# 1541-3.net
KiCad netlist of a schematic drawn in EAGLE
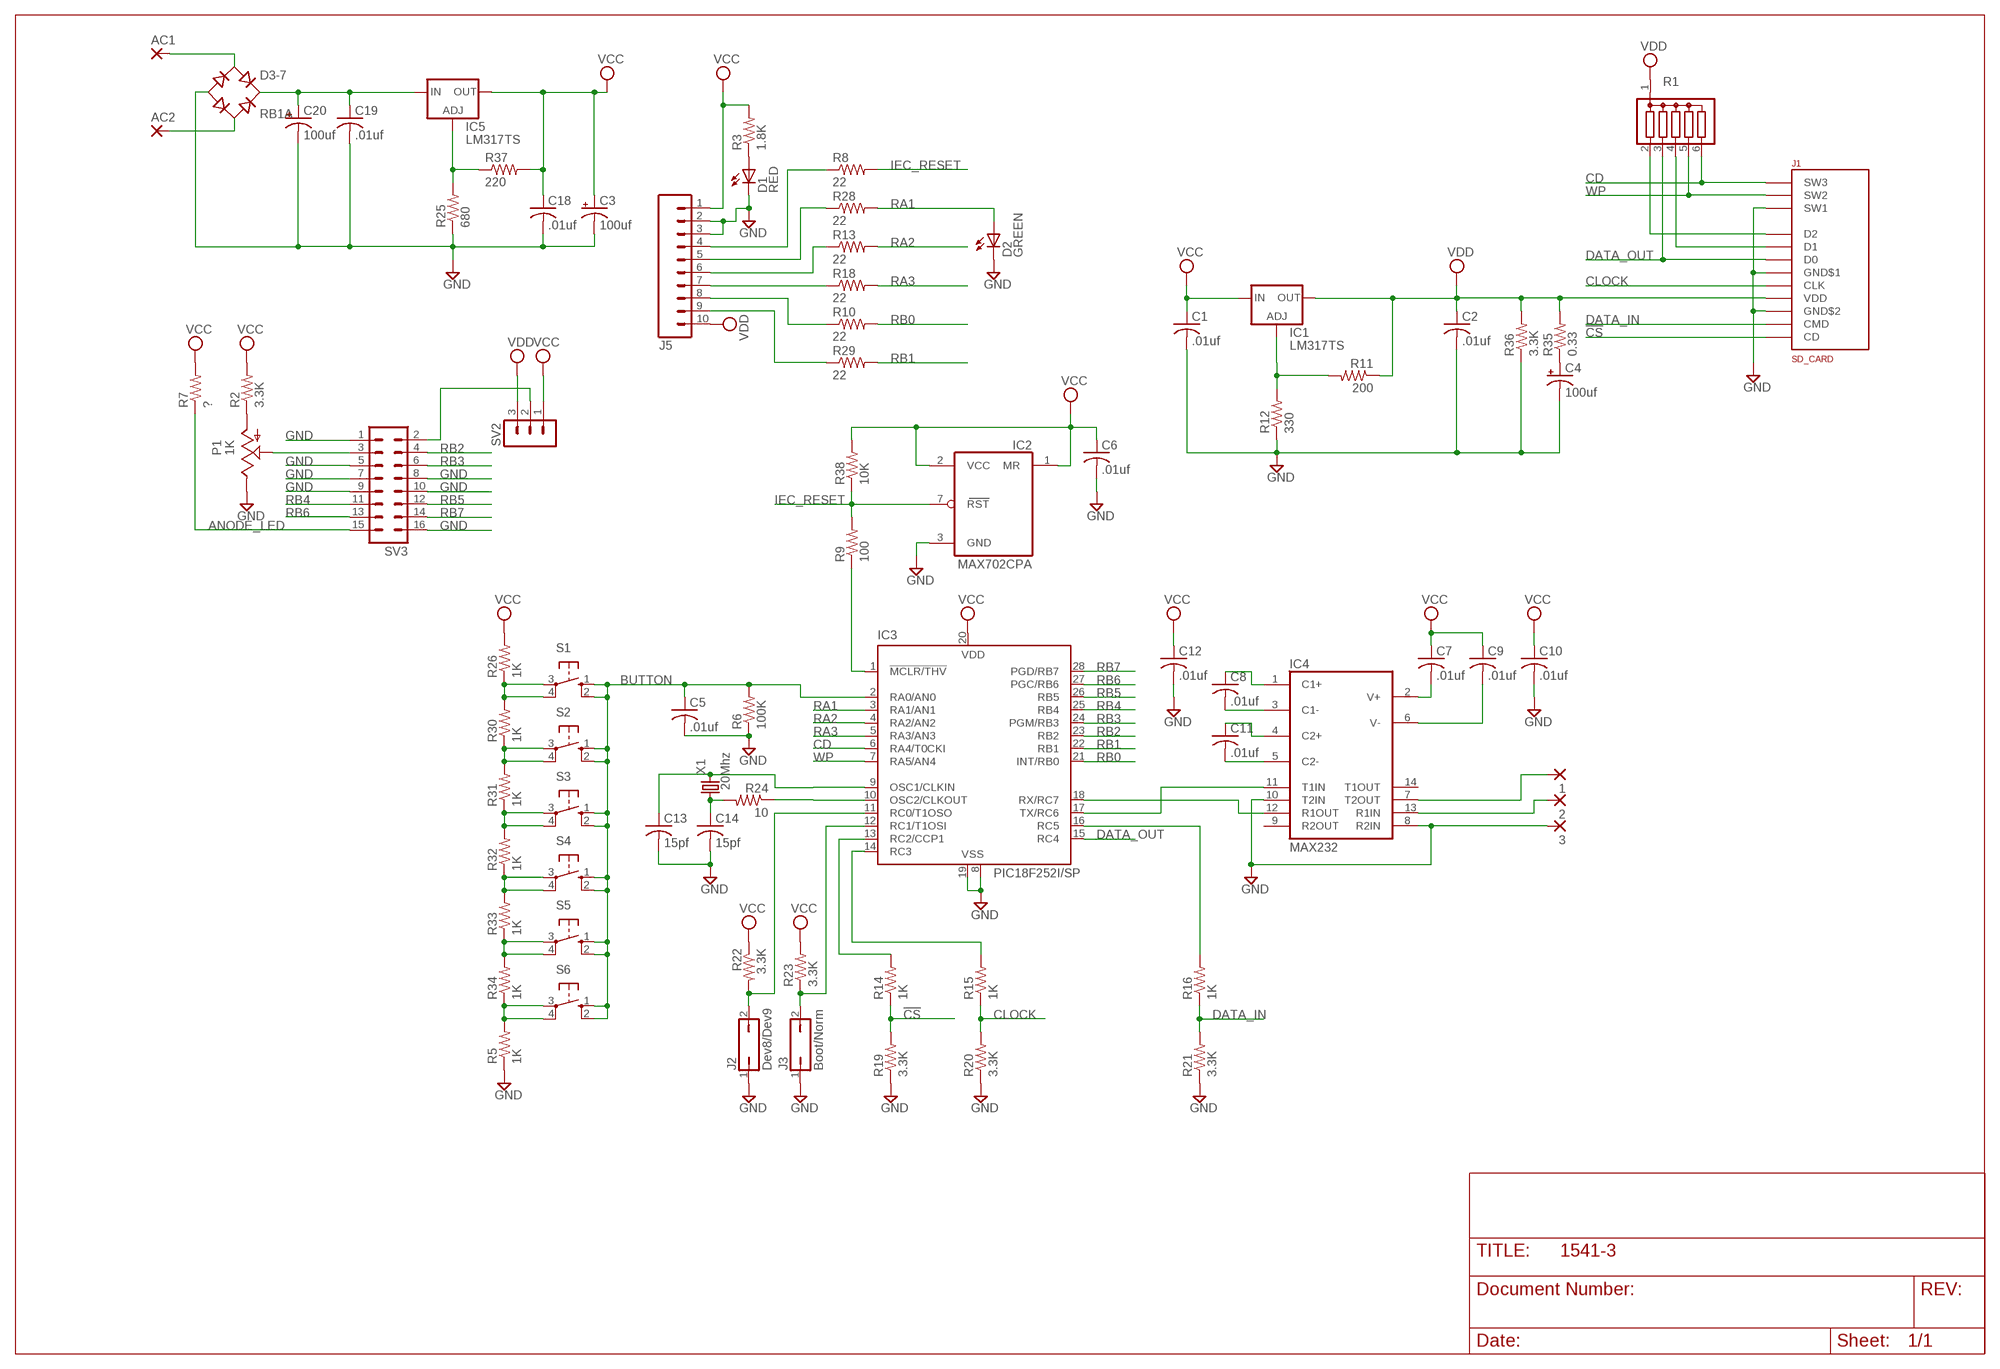
[diagram p0: schematic, sheet 1]

(export (version "E")
  (design (tool "Eeschema 10.0.6"))
  (components
    (comp (ref "1")
      (value "2,15/1,0")
      (footprint "eagle-import:2,15_1,0")
      (libsource (lib "eagle-import") (part "2,15/1,0"))
    )
    (comp (ref "2")
      (value "2,15/1,0")
      (footprint "eagle-import:2,15_1,0")
      (libsource (lib "eagle-import") (part "2,15/1,0"))
    )
    (comp (ref "3")
      (value "2,15/1,0")
      (footprint "eagle-import:2,15_1,0")
      (libsource (lib "eagle-import") (part "2,15/1,0"))
    )
    (comp (ref "AC1")
      (value "2,15/1,0")
      (footprint "eagle-import:2,15_1,0")
      (libsource (lib "eagle-import") (part "2,15/1,0"))
    )
    (comp (ref "AC2")
      (value "2,15/1,0")
      (footprint "eagle-import:2,15_1,0")
      (libsource (lib "eagle-import") (part "2,15/1,0"))
    )
    (comp (ref "C1")
      (value ".01uf")
      (footprint "eagle-import:C025-024X044")
      (libsource (lib "eagle-import") (part "C-US025-024X044"))
    )
    (comp (ref "C2")
      (value ".01uf")
      (footprint "eagle-import:C025-024X044")
      (libsource (lib "eagle-import") (part "C-US025-024X044"))
    )
    (comp (ref "C3")
      (value "100uf")
      (footprint "eagle-import:E2-5")
      (libsource (lib "eagle-import") (part "CPOL-USE2-5"))
    )
    (comp (ref "C4")
      (value "100uf")
      (footprint "eagle-import:E2-5")
      (libsource (lib "eagle-import") (part "CPOL-USE2-5"))
    )
    (comp (ref "C5")
      (value ".01uf")
      (footprint "eagle-import:C025-024X044")
      (libsource (lib "eagle-import") (part "C-US025-024X044"))
    )
    (comp (ref "C6")
      (value ".01uf")
      (footprint "eagle-import:C025-024X044")
      (libsource (lib "eagle-import") (part "C-US025-024X044"))
    )
    (comp (ref "C7")
      (value ".01uf")
      (footprint "eagle-import:C025-024X044")
      (libsource (lib "eagle-import") (part "C-US025-024X044"))
    )
    (comp (ref "C8")
      (value ".01uf")
      (footprint "eagle-import:C025-024X044")
      (libsource (lib "eagle-import") (part "C-US025-024X044"))
    )
    (comp (ref "C9")
      (value ".01uf")
      (footprint "eagle-import:C025-024X044")
      (libsource (lib "eagle-import") (part "C-US025-024X044"))
    )
    (comp (ref "C10")
      (value ".01uf")
      (footprint "eagle-import:C025-024X044")
      (libsource (lib "eagle-import") (part "C-US025-024X044"))
    )
    (comp (ref "C11")
      (value ".01uf")
      (footprint "eagle-import:C025-024X044")
      (libsource (lib "eagle-import") (part "C-US025-024X044"))
    )
    (comp (ref "C12")
      (value ".01uf")
      (footprint "eagle-import:C025-024X044")
      (libsource (lib "eagle-import") (part "C-US025-024X044"))
    )
    (comp (ref "C13")
      (value "15pf")
      (footprint "eagle-import:C025-024X044")
      (libsource (lib "eagle-import") (part "C-US025-024X044"))
    )
    (comp (ref "C14")
      (value "15pf")
      (footprint "eagle-import:C025-024X044")
      (libsource (lib "eagle-import") (part "C-US025-024X044"))
    )
    (comp (ref "C18")
      (value ".01uf")
      (footprint "eagle-import:C025-024X044")
      (libsource (lib "eagle-import") (part "C-US025-024X044"))
    )
    (comp (ref "C19")
      (value ".01uf")
      (footprint "eagle-import:C025-024X044")
      (libsource (lib "eagle-import") (part "C-US025-024X044"))
    )
    (comp (ref "C20")
      (value "100uf")
      (footprint "eagle-import:E2-5")
      (libsource (lib "eagle-import") (part "CPOL-USE2-5"))
    )
    (comp (ref "D1")
      (value "RED")
      (footprint "eagle-import:LED3MM")
      (libsource (lib "eagle-import") (part "LED3MM"))
    )
    (comp (ref "D2")
      (value "GREEN")
      (footprint "eagle-import:LED3MM")
      (libsource (lib "eagle-import") (part "LED3MM"))
    )
    (comp (ref "D3-7")
      (value "RB1A")
      (footprint "eagle-import:RB1A")
      (libsource (lib "eagle-import") (part "RB1A"))
    )
    (comp (ref "IC1")
      (value "LM317TS")
      (footprint "eagle-import:317TS")
      (libsource (lib "eagle-import") (part "LM317TS"))
    )
    (comp (ref "IC2")
      (value "MAX702CPA")
      (footprint "eagle-import:DIL08")
      (fields (field (name "MF") "MAXIM") (field (name "MPN") "MAX702CPA+"))
      (libsource (lib "eagle-import") (part "MAX702CPA"))
    )
    (comp (ref "IC3")
      (value "PIC18F252I/SP")
      (footprint "eagle-import:DIL28-3")
      (fields (field (name "MF") "MICROCHIP") (field (name "MPN") "PIC16F870-I/SP"))
      (libsource (lib "eagle-import") (part "PIC16870PF"))
    )
    (comp (ref "IC4")
      (value "MAX232")
      (footprint "eagle-import:DIL16")
      (fields (field (name "MF") "MAXIM") (field (name "MPN") "MAX232ACPE+"))
      (libsource (lib "eagle-import") (part "MAX232"))
    )
    (comp (ref "IC5")
      (value "LM317TS")
      (footprint "eagle-import:317TS")
      (libsource (lib "eagle-import") (part "LM317TS"))
    )
    (comp (ref "J1")
      (value "SD_CARD")
      (footprint "eagle-import:SD_CARD")
      (libsource (lib "eagle-import") (part "SD_CARD"))
    )
    (comp (ref "J2")
      (value "Dev8/Dev9")
      (footprint "eagle-import:JP1")
      (libsource (lib "eagle-import") (part "JP1Q"))
    )
    (comp (ref "J3")
      (value "Boot/Norm")
      (footprint "eagle-import:JP1")
      (libsource (lib "eagle-import") (part "JP1Q"))
    )
    (comp (ref "J5")
      (value "M10")
      (footprint "eagle-import:10P")
      (libsource (lib "eagle-import") (part "M10"))
    )
    (comp (ref "P1")
      (value "1K")
      (footprint "eagle-import:LI10")
      (libsource (lib "eagle-import") (part "TRIM_US-LI10"))
    )
    (comp (ref "R1")
      (value "G05R")
      (footprint "eagle-import:SIL6")
      (libsource (lib "eagle-import") (part "G05R"))
    )
    (comp (ref "R2")
      (value "3.3K")
      (footprint "eagle-import:0207_2V")
      (libsource (lib "eagle-import") (part "R-US_0207/2V"))
    )
    (comp (ref "R3")
      (value "1.8K")
      (footprint "eagle-import:0207_2V")
      (libsource (lib "eagle-import") (part "R-US_0207/2V"))
    )
    (comp (ref "R5")
      (value "1K")
      (footprint "eagle-import:0207_2V")
      (libsource (lib "eagle-import") (part "R-US_0207/2V"))
    )
    (comp (ref "R6")
      (value "100K")
      (footprint "eagle-import:0207_2V")
      (libsource (lib "eagle-import") (part "R-US_0207/2V"))
    )
    (comp (ref "R7")
      (value "?")
      (footprint "eagle-import:0207_2V")
      (libsource (lib "eagle-import") (part "R-US_0207/2V"))
    )
    (comp (ref "R8")
      (value "22")
      (footprint "eagle-import:0207_2V")
      (libsource (lib "eagle-import") (part "R-US_0207/2V"))
    )
    (comp (ref "R9")
      (value "100")
      (footprint "eagle-import:0207_2V")
      (libsource (lib "eagle-import") (part "R-US_0207/2V"))
    )
    (comp (ref "R10")
      (value "22")
      (footprint "eagle-import:0207_2V")
      (libsource (lib "eagle-import") (part "R-US_0207/2V"))
    )
    (comp (ref "R11")
      (value "200")
      (footprint "eagle-import:0207_2V")
      (libsource (lib "eagle-import") (part "R-US_0207/2V"))
    )
    (comp (ref "R12")
      (value "330")
      (footprint "eagle-import:0207_2V")
      (libsource (lib "eagle-import") (part "R-US_0207/2V"))
    )
    (comp (ref "R13")
      (value "22")
      (footprint "eagle-import:0207_2V")
      (libsource (lib "eagle-import") (part "R-US_0207/2V"))
    )
    (comp (ref "R14")
      (value "1K")
      (footprint "eagle-import:0207_2V")
      (libsource (lib "eagle-import") (part "R-US_0207/2V"))
    )
    (comp (ref "R15")
      (value "1K")
      (footprint "eagle-import:0207_2V")
      (libsource (lib "eagle-import") (part "R-US_0207/2V"))
    )
    (comp (ref "R16")
      (value "1K")
      (footprint "eagle-import:0207_2V")
      (libsource (lib "eagle-import") (part "R-US_0207/2V"))
    )
    (comp (ref "R18")
      (value "22")
      (footprint "eagle-import:0207_2V")
      (libsource (lib "eagle-import") (part "R-US_0207/2V"))
    )
    (comp (ref "R19")
      (value "3.3K")
      (footprint "eagle-import:0207_2V")
      (libsource (lib "eagle-import") (part "R-US_0207/2V"))
    )
    (comp (ref "R20")
      (value "3.3K")
      (footprint "eagle-import:0207_2V")
      (libsource (lib "eagle-import") (part "R-US_0207/2V"))
    )
    (comp (ref "R21")
      (value "3.3K")
      (footprint "eagle-import:0207_2V")
      (libsource (lib "eagle-import") (part "R-US_0207/2V"))
    )
    (comp (ref "R22")
      (value "3.3K")
      (footprint "eagle-import:0207_2V")
      (libsource (lib "eagle-import") (part "R-US_0207/2V"))
    )
    (comp (ref "R23")
      (value "3.3K")
      (footprint "eagle-import:0207_2V")
      (libsource (lib "eagle-import") (part "R-US_0207/2V"))
    )
    (comp (ref "R24")
      (value "10")
      (footprint "eagle-import:0207_2V")
      (libsource (lib "eagle-import") (part "R-US_0207/2V"))
    )
    (comp (ref "R25")
      (value "680")
      (footprint "eagle-import:0207_2V")
      (libsource (lib "eagle-import") (part "R-US_0207/2V"))
    )
    (comp (ref "R26")
      (value "1K")
      (footprint "eagle-import:0207_2V")
      (libsource (lib "eagle-import") (part "R-US_0207/2V"))
    )
    (comp (ref "R28")
      (value "22")
      (footprint "eagle-import:0207_2V")
      (libsource (lib "eagle-import") (part "R-US_0207/2V"))
    )
    (comp (ref "R29")
      (value "22")
      (footprint "eagle-import:0207_2V")
      (libsource (lib "eagle-import") (part "R-US_0207/2V"))
    )
    (comp (ref "R30")
      (value "1K")
      (footprint "eagle-import:0207_2V")
      (libsource (lib "eagle-import") (part "R-US_0207/2V"))
    )
    (comp (ref "R31")
      (value "1K")
      (footprint "eagle-import:0207_2V")
      (libsource (lib "eagle-import") (part "R-US_0207/2V"))
    )
    (comp (ref "R32")
      (value "1K")
      (footprint "eagle-import:0207_2V")
      (libsource (lib "eagle-import") (part "R-US_0207/2V"))
    )
    (comp (ref "R33")
      (value "1K")
      (footprint "eagle-import:0207_2V")
      (libsource (lib "eagle-import") (part "R-US_0207/2V"))
    )
    (comp (ref "R34")
      (value "1K")
      (footprint "eagle-import:0207_2V")
      (libsource (lib "eagle-import") (part "R-US_0207/2V"))
    )
    (comp (ref "R35")
      (value "0.33")
      (footprint "eagle-import:0207_2V")
      (libsource (lib "eagle-import") (part "R-US_0207/2V"))
    )
    (comp (ref "R36")
      (value "3.3K")
      (footprint "eagle-import:0207_2V")
      (libsource (lib "eagle-import") (part "R-US_0207/2V"))
    )
    (comp (ref "R37")
      (value "220")
      (footprint "eagle-import:0207_2V")
      (libsource (lib "eagle-import") (part "R-US_0207/2V"))
    )
    (comp (ref "R38")
      (value "10K")
      (footprint "eagle-import:0207_2V")
      (libsource (lib "eagle-import") (part "R-US_0207/2V"))
    )
    (comp (ref "S1")
      (value "10-XX")
      (footprint "eagle-import:B3F-10XX")
      (fields (field (name "MPN") "B3F-1000"))
      (libsource (lib "eagle-import") (part "10-XX"))
    )
    (comp (ref "S2")
      (value "10-XX")
      (footprint "eagle-import:B3F-10XX")
      (fields (field (name "MPN") "B3F-1000"))
      (libsource (lib "eagle-import") (part "10-XX"))
    )
    (comp (ref "S3")
      (value "10-XX")
      (footprint "eagle-import:B3F-10XX")
      (fields (field (name "MPN") "B3F-1000"))
      (libsource (lib "eagle-import") (part "10-XX"))
    )
    (comp (ref "S4")
      (value "10-XX")
      (footprint "eagle-import:B3F-10XX")
      (fields (field (name "MPN") "B3F-1000"))
      (libsource (lib "eagle-import") (part "10-XX"))
    )
    (comp (ref "S5")
      (value "10-XX")
      (footprint "eagle-import:B3F-10XX")
      (fields (field (name "MPN") "B3F-1000"))
      (libsource (lib "eagle-import") (part "10-XX"))
    )
    (comp (ref "S6")
      (value "10-XX")
      (footprint "eagle-import:B3F-10XX")
      (fields (field (name "MPN") "B3F-1000"))
      (libsource (lib "eagle-import") (part "10-XX"))
    )
    (comp (ref "SV2")
      (value "MA03-1")
      (footprint "eagle-import:MA03-1")
      (libsource (lib "eagle-import") (part "MA03-1"))
    )
    (comp (ref "SV3")
      (value "ML16")
      (footprint "eagle-import:ML16")
      (libsource (lib "eagle-import") (part "ML16"))
    )
    (comp (ref "X1")
      (value "20Mhz")
      (footprint "eagle-import:HC49U70")
      (libsource (lib "eagle-import") (part "CRYSTALHC49U70"))
    )
  )
  (nets
    (net (code "1") (name "/ANODE_LED") (class "Default")
      (node (ref "R7") (pin "1") (pinfunction "1_1") (pintype "passive"))
      (node (ref "SV3") (pin "15") (pinfunction "15_15") (pintype "passive"))
    )
    (net (code "2") (name "/BUTTON") (class "Default")
      (node (ref "C5") (pin "1") (pinfunction "1_1") (pintype "passive"))
      (node (ref "IC3") (pin "2") (pinfunction "RA0/AN0_2") (pintype "bidirectional"))
      (node (ref "R6") (pin "2") (pinfunction "2_2") (pintype "passive"))
      (node (ref "S1") (pin "1") (pinfunction "S_1") (pintype "passive"))
      (node (ref "S1") (pin "2") (pinfunction "S1_2") (pintype "passive"))
      (node (ref "S2") (pin "1") (pinfunction "S_1") (pintype "passive"))
      (node (ref "S2") (pin "2") (pinfunction "S1_2") (pintype "passive"))
      (node (ref "S3") (pin "1") (pinfunction "S_1") (pintype "passive"))
      (node (ref "S3") (pin "2") (pinfunction "S1_2") (pintype "passive"))
      (node (ref "S4") (pin "1") (pinfunction "S_1") (pintype "passive"))
      (node (ref "S4") (pin "2") (pinfunction "S1_2") (pintype "passive"))
      (node (ref "S5") (pin "1") (pinfunction "S_1") (pintype "passive"))
      (node (ref "S5") (pin "2") (pinfunction "S1_2") (pintype "passive"))
      (node (ref "S6") (pin "1") (pinfunction "S_1") (pintype "passive"))
      (node (ref "S6") (pin "2") (pinfunction "S1_2") (pintype "passive"))
    )
    (net (code "3") (name "/CD") (class "Default")
      (node (ref "IC3") (pin "6") (pinfunction "RA4/T0CKI_6") (pintype "bidirectional"))
      (node (ref "J1") (pin "SW3") (pinfunction "SW3_SW3") (pintype "output"))
      (node (ref "R1") (pin "6") (pinfunction "6_6") (pintype "passive"))
    )
    (net (code "4") (name "/CLOCK") (class "Default")
      (node (ref "J1") (pin "CLK") (pinfunction "CLK_CLK") (pintype "input"))
      (node (ref "R15") (pin "1") (pinfunction "1_1") (pintype "passive"))
      (node (ref "R20") (pin "2") (pinfunction "2_2") (pintype "passive"))
    )
    (net (code "5") (name "/DATA_IN") (class "Default")
      (node (ref "J1") (pin "CMD") (pinfunction "CMD_CMD") (pintype "input"))
      (node (ref "R16") (pin "1") (pinfunction "1_1") (pintype "passive"))
      (node (ref "R21") (pin "2") (pinfunction "2_2") (pintype "passive"))
    )
    (net (code "6") (name "/DATA_OUT") (class "Default")
      (node (ref "IC3") (pin "15") (pinfunction "RC4_15") (pintype "bidirectional"))
      (node (ref "J1") (pin "DAT0") (pinfunction "D0_DAT0") (pintype "output"))
      (node (ref "R1") (pin "3") (pinfunction "3_3") (pintype "passive"))
    )
    (net (code "7") (name "/IEC_RESET") (class "Default")
      (node (ref "IC2") (pin "7") (pinfunction "RST_7") (pintype "output"))
      (node (ref "R38") (pin "1") (pinfunction "1_1") (pintype "passive"))
      (node (ref "R8") (pin "2") (pinfunction "2_2") (pintype "passive"))
      (node (ref "R9") (pin "2") (pinfunction "2_2") (pintype "passive"))
    )
    (net (code "8") (name "/RA1") (class "Default")
      (node (ref "D2") (pin "A") (pinfunction "A_A") (pintype "passive"))
      (node (ref "IC3") (pin "3") (pinfunction "RA1/AN1_3") (pintype "bidirectional"))
      (node (ref "R28") (pin "2") (pinfunction "2_2") (pintype "passive"))
    )
    (net (code "9") (name "/RA2") (class "Default")
      (node (ref "IC3") (pin "4") (pinfunction "RA2/AN2_4") (pintype "bidirectional"))
      (node (ref "R13") (pin "2") (pinfunction "2_2") (pintype "passive"))
    )
    (net (code "10") (name "/RA3") (class "Default")
      (node (ref "IC3") (pin "5") (pinfunction "RA3/AN3_5") (pintype "bidirectional"))
      (node (ref "R18") (pin "2") (pinfunction "2_2") (pintype "passive"))
    )
    (net (code "11") (name "/RB0") (class "Default")
      (node (ref "IC3") (pin "21") (pinfunction "INT/RB0_21") (pintype "bidirectional"))
      (node (ref "R10") (pin "2") (pinfunction "2_2") (pintype "passive"))
    )
    (net (code "12") (name "/RB1") (class "Default")
      (node (ref "IC3") (pin "22") (pinfunction "RB1_22") (pintype "bidirectional"))
      (node (ref "R29") (pin "2") (pinfunction "2_2") (pintype "passive"))
    )
    (net (code "13") (name "/RB2") (class "Default")
      (node (ref "IC3") (pin "23") (pinfunction "RB2_23") (pintype "bidirectional"))
      (node (ref "SV3") (pin "4") (pinfunction "4_4") (pintype "passive"))
    )
    (net (code "14") (name "/RB3") (class "Default")
      (node (ref "IC3") (pin "24") (pinfunction "PGM/RB3_24") (pintype "bidirectional"))
      (node (ref "SV3") (pin "6") (pinfunction "6_6") (pintype "passive"))
    )
    (net (code "15") (name "/RB4") (class "Default")
      (node (ref "IC3") (pin "25") (pinfunction "RB4_25") (pintype "bidirectional"))
      (node (ref "SV3") (pin "11") (pinfunction "11_11") (pintype "passive"))
    )
    (net (code "16") (name "/RB5") (class "Default")
      (node (ref "IC3") (pin "26") (pinfunction "RB5_26") (pintype "bidirectional"))
      (node (ref "SV3") (pin "12") (pinfunction "12_12") (pintype "passive"))
    )
    (net (code "17") (name "/RB6") (class "Default")
      (node (ref "IC3") (pin "27") (pinfunction "PGC/RB6_27") (pintype "bidirectional"))
      (node (ref "SV3") (pin "13") (pinfunction "13_13") (pintype "passive"))
    )
    (net (code "18") (name "/RB7") (class "Default")
      (node (ref "IC3") (pin "28") (pinfunction "PGD/RB7_28") (pintype "bidirectional"))
      (node (ref "SV3") (pin "14") (pinfunction "14_14") (pintype "passive"))
    )
    (net (code "19") (name "/WP") (class "Default")
      (node (ref "IC3") (pin "7") (pinfunction "RA5/AN4_7") (pintype "bidirectional"))
      (node (ref "J1") (pin "SW2") (pinfunction "SW2_SW2") (pintype "output"))
      (node (ref "R1") (pin "5") (pinfunction "5_5") (pintype "passive"))
    )
    (net (code "20") (name "/~{CS}") (class "Default")
      (node (ref "J1") (pin "DAT3") (pinfunction "CD_DAT3") (pintype "input"))
      (node (ref "R14") (pin "1") (pinfunction "1_1") (pintype "passive"))
      (node (ref "R19") (pin "2") (pinfunction "2_2") (pintype "passive"))
    )
    (net (code "21") (name "GND") (class "Default")
      (node (ref "3") (pin "1") (pinfunction "P_1") (pintype "passive"))
      (node (ref "C1") (pin "2") (pinfunction "2_2") (pintype "passive"))
      (node (ref "C10") (pin "2") (pinfunction "2_2") (pintype "passive"))
      (node (ref "C12") (pin "2") (pinfunction "2_2") (pintype "passive"))
      (node (ref "C13") (pin "2") (pinfunction "2_2") (pintype "passive"))
      (node (ref "C14") (pin "2") (pinfunction "2_2") (pintype "passive"))
      (node (ref "C18") (pin "2") (pinfunction "2_2") (pintype "passive"))
      (node (ref "C19") (pin "2") (pinfunction "2_2") (pintype "passive"))
      (node (ref "C2") (pin "2") (pinfunction "2_2") (pintype "passive"))
      (node (ref "C20") (pin "-") (pinfunction "-_-") (pintype "passive"))
      (node (ref "C3") (pin "-") (pinfunction "-_-") (pintype "passive"))
      (node (ref "C4") (pin "-") (pinfunction "-_-") (pintype "passive"))
      (node (ref "C5") (pin "2") (pinfunction "2_2") (pintype "passive"))
      (node (ref "C6") (pin "2") (pinfunction "2_2") (pintype "passive"))
      (node (ref "D1") (pin "K") (pinfunction "C_K") (pintype "passive"))
      (node (ref "D2") (pin "K") (pinfunction "C_K") (pintype "passive"))
      (node (ref "D3-7") (pin "-") (pinfunction "-_-") (pintype "passive"))
      (node (ref "IC2") (pin "3") (pinfunction "GND_3") (pintype "power_in"))
      (node (ref "IC3") (pin "19") (pinfunction "VSS_19") (pintype "power_in"))
      (node (ref "IC3") (pin "8") (pinfunction "VSS_8") (pintype "power_in"))
      (node (ref "IC4") (pin "10") (pinfunction "T2IN_10") (pintype "input"))
      (node (ref "IC4") (pin "8") (pinfunction "R2IN_8") (pintype "input"))
      (node (ref "J1") (pin "SW1") (pinfunction "SW1_SW1") (pintype "input"))
      (node (ref "J1") (pin "VSS$1") (pinfunction "GND$1_VSS$1") (pintype "power_in"))
      (node (ref "J1") (pin "VSS$2") (pinfunction "GND$2_VSS$2") (pintype "power_in"))
      (node (ref "J2") (pin "1") (pinfunction "1_1") (pintype "passive"))
      (node (ref "J3") (pin "1") (pinfunction "1_1") (pintype "passive"))
      (node (ref "J5") (pin "2") (pinfunction "2_2") (pintype "passive"))
      (node (ref "J5") (pin "3") (pinfunction "3_3") (pintype "passive"))
      (node (ref "P1") (pin "E") (pinfunction "E_E") (pintype "passive"))
      (node (ref "R12") (pin "1") (pinfunction "1_1") (pintype "passive"))
      (node (ref "R19") (pin "1") (pinfunction "1_1") (pintype "passive"))
      (node (ref "R20") (pin "1") (pinfunction "1_1") (pintype "passive"))
      (node (ref "R21") (pin "1") (pinfunction "1_1") (pintype "passive"))
      (node (ref "R25") (pin "1") (pinfunction "1_1") (pintype "passive"))
      (node (ref "R36") (pin "1") (pinfunction "1_1") (pintype "passive"))
      (node (ref "R5") (pin "1") (pinfunction "1_1") (pintype "passive"))
      (node (ref "R6") (pin "1") (pinfunction "1_1") (pintype "passive"))
      (node (ref "SV3") (pin "1") (pinfunction "1_1") (pintype "passive"))
      (node (ref "SV3") (pin "10") (pinfunction "10_10") (pintype "passive"))
      (node (ref "SV3") (pin "16") (pinfunction "16_16") (pintype "passive"))
      (node (ref "SV3") (pin "5") (pinfunction "5_5") (pintype "passive"))
      (node (ref "SV3") (pin "7") (pinfunction "7_7") (pintype "passive"))
      (node (ref "SV3") (pin "8") (pinfunction "8_8") (pintype "passive"))
      (node (ref "SV3") (pin "9") (pinfunction "9_9") (pintype "passive"))
    )
    (net (code "22") (name "Net-(1-P)") (class "Default")
      (node (ref "1") (pin "1") (pinfunction "P_1") (pintype "passive"))
      (node (ref "IC4") (pin "7") (pinfunction "T2OUT_7") (pintype "output"))
    )
    (net (code "23") (name "Net-(2-P)") (class "Default")
      (node (ref "2") (pin "1") (pinfunction "P_1") (pintype "passive"))
      (node (ref "IC4") (pin "13") (pinfunction "R1IN_13") (pintype "input"))
    )
    (net (code "24") (name "Net-(AC1-P)") (class "Default")
      (node (ref "AC1") (pin "1") (pinfunction "P_1") (pintype "passive"))
      (node (ref "D3-7") (pin "AC1") (pinfunction "AC1_AC1") (pintype "passive"))
    )
    (net (code "25") (name "Net-(AC2-P)") (class "Default")
      (node (ref "AC2") (pin "1") (pinfunction "P_1") (pintype "passive"))
      (node (ref "D3-7") (pin "AC2") (pinfunction "AC2_AC2") (pintype "passive"))
    )
    (net (code "26") (name "Net-(C4-Pad+)") (class "Default")
      (node (ref "C4") (pin "+") (pinfunction "+_+") (pintype "passive"))
      (node (ref "R35") (pin "1") (pinfunction "1_1") (pintype "passive"))
    )
    (net (code "27") (name "Net-(C14-Pad1)") (class "Default")
      (node (ref "C14") (pin "1") (pinfunction "1_1") (pintype "passive"))
      (node (ref "R24") (pin "2") (pinfunction "2_2") (pintype "passive"))
      (node (ref "X1") (pin "1") (pinfunction "1_1") (pintype "passive"))
    )
    (net (code "28") (name "Net-(D1-PadA)") (class "Default")
      (node (ref "D1") (pin "A") (pinfunction "A_A") (pintype "passive"))
      (node (ref "R3") (pin "1") (pinfunction "1_1") (pintype "passive"))
    )
    (net (code "29") (name "Net-(IC1-ADJ)") (class "Default")
      (node (ref "IC1") (pin "1") (pinfunction "ADJ_1") (pintype "input"))
      (node (ref "R11") (pin "2") (pinfunction "2_2") (pintype "passive"))
      (node (ref "R12") (pin "2") (pinfunction "2_2") (pintype "passive"))
    )
    (net (code "30") (name "Net-(IC3-OSC1{slash}CLKIN)") (class "Default")
      (node (ref "C13") (pin "1") (pinfunction "1_1") (pintype "passive"))
      (node (ref "IC3") (pin "9") (pinfunction "OSC1/CLKIN_9") (pintype "input"))
      (node (ref "X1") (pin "2") (pinfunction "2_2") (pintype "passive"))
    )
    (net (code "31") (name "Net-(IC3-OSC2{slash}CLKOUT)") (class "Default")
      (node (ref "IC3") (pin "10") (pinfunction "OSC2/CLKOUT_10") (pintype "output"))
      (node (ref "R24") (pin "1") (pinfunction "1_1") (pintype "passive"))
    )
    (net (code "32") (name "Net-(IC3-RC0{slash}T1OSO)") (class "Default")
      (node (ref "IC3") (pin "11") (pinfunction "RC0/T1OSO_11") (pintype "bidirectional"))
      (node (ref "J2") (pin "2") (pinfunction "2_2") (pintype "passive"))
      (node (ref "R22") (pin "2") (pinfunction "2_2") (pintype "passive"))
    )
    (net (code "33") (name "Net-(IC3-RC1{slash}T1OSI)") (class "Default")
      (node (ref "IC3") (pin "12") (pinfunction "RC1/T1OSI_12") (pintype "bidirectional"))
      (node (ref "J3") (pin "2") (pinfunction "2_2") (pintype "passive"))
      (node (ref "R23") (pin "1") (pinfunction "1_1") (pintype "passive"))
    )
    (net (code "34") (name "Net-(IC3-RC2{slash}CCP1)") (class "Default")
      (node (ref "IC3") (pin "13") (pinfunction "RC2/CCP1_13") (pintype "bidirectional"))
      (node (ref "R14") (pin "2") (pinfunction "2_2") (pintype "passive"))
    )
    (net (code "35") (name "Net-(IC3-RC3)") (class "Default")
      (node (ref "IC3") (pin "14") (pinfunction "RC3_14") (pintype "bidirectional"))
      (node (ref "R15") (pin "2") (pinfunction "2_2") (pintype "passive"))
    )
    (net (code "36") (name "Net-(IC3-RC5)") (class "Default")
      (node (ref "IC3") (pin "16") (pinfunction "RC5_16") (pintype "bidirectional"))
      (node (ref "R16") (pin "2") (pinfunction "2_2") (pintype "passive"))
    )
    (net (code "37") (name "Net-(IC3-RX{slash}RC7)") (class "Default")
      (node (ref "IC3") (pin "18") (pinfunction "RX/RC7_18") (pintype "bidirectional"))
      (node (ref "IC4") (pin "12") (pinfunction "R1OUT_12") (pintype "output"))
    )
    (net (code "38") (name "Net-(IC3-TX{slash}RC6)") (class "Default")
      (node (ref "IC3") (pin "17") (pinfunction "TX/RC6_17") (pintype "bidirectional"))
      (node (ref "IC4") (pin "11") (pinfunction "T1IN_11") (pintype "input"))
    )
    (net (code "39") (name "Net-(IC3-~{MCLR{slash}THV})") (class "Default")
      (node (ref "IC3") (pin "1") (pinfunction "~{MCLR/THV}_1") (pintype "input"))
      (node (ref "R9") (pin "1") (pinfunction "1_1") (pintype "passive"))
    )
    (net (code "40") (name "Net-(IC4A-C1+)") (class "Default")
      (node (ref "C8") (pin "1") (pinfunction "1_1") (pintype "passive"))
      (node (ref "IC4") (pin "1") (pinfunction "C1+_1") (pintype "bidirectional"))
    )
    (net (code "41") (name "Net-(IC4A-C1-)") (class "Default")
      (node (ref "C8") (pin "2") (pinfunction "2_2") (pintype "passive"))
      (node (ref "IC4") (pin "3") (pinfunction "C1-_3") (pintype "bidirectional"))
    )
    (net (code "42") (name "Net-(IC4A-C2+)") (class "Default")
      (node (ref "C11") (pin "1") (pinfunction "1_1") (pintype "passive"))
      (node (ref "IC4") (pin "4") (pinfunction "C2+_4") (pintype "bidirectional"))
    )
    (net (code "43") (name "Net-(IC4A-C2-)") (class "Default")
      (node (ref "C11") (pin "2") (pinfunction "2_2") (pintype "passive"))
      (node (ref "IC4") (pin "5") (pinfunction "C2-_5") (pintype "bidirectional"))
    )
    (net (code "44") (name "Net-(IC4A-V+)") (class "Default")
      (node (ref "C7") (pin "2") (pinfunction "2_2") (pintype "passive"))
      (node (ref "IC4") (pin "2") (pinfunction "V+_2") (pintype "bidirectional"))
    )
    (net (code "45") (name "Net-(IC4A-V-)") (class "Default")
      (node (ref "C9") (pin "2") (pinfunction "2_2") (pintype "passive"))
      (node (ref "IC4") (pin "6") (pinfunction "V-_6") (pintype "bidirectional"))
    )
    (net (code "46") (name "Net-(IC5-ADJ)") (class "Default")
      (node (ref "IC5") (pin "1") (pinfunction "ADJ_1") (pintype "input"))
      (node (ref "R25") (pin "2") (pinfunction "2_2") (pintype "passive"))
      (node (ref "R37") (pin "1") (pinfunction "1_1") (pintype "passive"))
    )
    (net (code "47") (name "Net-(IC5-IN)") (class "Default")
      (node (ref "C19") (pin "1") (pinfunction "1_1") (pintype "passive"))
      (node (ref "C20") (pin "+") (pinfunction "+_+") (pintype "passive"))
      (node (ref "D3-7") (pin "+") (pinfunction "+_+") (pintype "passive"))
      (node (ref "IC5") (pin "3") (pinfunction "IN_3") (pintype "input"))
    )
    (net (code "48") (name "Net-(J1-D1)") (class "Default")
      (node (ref "J1") (pin "DAT1") (pinfunction "D1_DAT1") (pintype "output"))
      (node (ref "R1") (pin "4") (pinfunction "4_4") (pintype "passive"))
    )
    (net (code "49") (name "Net-(J1-D2)") (class "Default")
      (node (ref "J1") (pin "DAT2") (pinfunction "D2_DAT2") (pintype "output"))
      (node (ref "R1") (pin "2") (pinfunction "2_2") (pintype "passive"))
    )
    (net (code "50") (name "Net-(J5-Pad4)") (class "Default")
      (node (ref "J5") (pin "4") (pinfunction "4_4") (pintype "passive"))
      (node (ref "R8") (pin "1") (pinfunction "1_1") (pintype "passive"))
    )
    (net (code "51") (name "Net-(J5-Pad5)") (class "Default")
      (node (ref "J5") (pin "5") (pinfunction "5_5") (pintype "passive"))
      (node (ref "R28") (pin "1") (pinfunction "1_1") (pintype "passive"))
    )
    (net (code "52") (name "Net-(J5-Pad6)") (class "Default")
      (node (ref "J5") (pin "6") (pinfunction "6_6") (pintype "passive"))
      (node (ref "R13") (pin "1") (pinfunction "1_1") (pintype "passive"))
    )
    (net (code "53") (name "Net-(J5-Pad7)") (class "Default")
      (node (ref "J5") (pin "7") (pinfunction "7_7") (pintype "passive"))
      (node (ref "R18") (pin "1") (pinfunction "1_1") (pintype "passive"))
    )
    (net (code "54") (name "Net-(J5-Pad8)") (class "Default")
      (node (ref "J5") (pin "8") (pinfunction "8_8") (pintype "passive"))
      (node (ref "R10") (pin "1") (pinfunction "1_1") (pintype "passive"))
    )
    (net (code "55") (name "Net-(J5-Pad9)") (class "Default")
      (node (ref "J5") (pin "9") (pinfunction "9_9") (pintype "passive"))
      (node (ref "R29") (pin "1") (pinfunction "1_1") (pintype "passive"))
    )
    (net (code "56") (name "Net-(P1-PadA)") (class "Default")
      (node (ref "P1") (pin "A") (pinfunction "A_A") (pintype "passive"))
      (node (ref "R2") (pin "1") (pinfunction "1_1") (pintype "passive"))
    )
    (net (code "57") (name "Net-(P1-PadS)") (class "Default")
      (node (ref "P1") (pin "S") (pinfunction "S_S") (pintype "passive"))
      (node (ref "SV3") (pin "3") (pinfunction "3_3") (pintype "passive"))
    )
    (net (code "58") (name "Net-(S1-P)") (class "Default")
      (node (ref "R26") (pin "1") (pinfunction "1_1") (pintype "passive"))
      (node (ref "R30") (pin "2") (pinfunction "2_2") (pintype "passive"))
      (node (ref "S1") (pin "3") (pinfunction "P_3") (pintype "passive"))
      (node (ref "S1") (pin "4") (pinfunction "P1_4") (pintype "passive"))
    )
    (net (code "59") (name "Net-(S2-P)") (class "Default")
      (node (ref "R30") (pin "1") (pinfunction "1_1") (pintype "passive"))
      (node (ref "R31") (pin "2") (pinfunction "2_2") (pintype "passive"))
      (node (ref "S2") (pin "3") (pinfunction "P_3") (pintype "passive"))
      (node (ref "S2") (pin "4") (pinfunction "P1_4") (pintype "passive"))
    )
    (net (code "60") (name "Net-(S3-P)") (class "Default")
      (node (ref "R31") (pin "1") (pinfunction "1_1") (pintype "passive"))
      (node (ref "R32") (pin "2") (pinfunction "2_2") (pintype "passive"))
      (node (ref "S3") (pin "3") (pinfunction "P_3") (pintype "passive"))
      (node (ref "S3") (pin "4") (pinfunction "P1_4") (pintype "passive"))
    )
    (net (code "61") (name "Net-(S4-P)") (class "Default")
      (node (ref "R32") (pin "1") (pinfunction "1_1") (pintype "passive"))
      (node (ref "R33") (pin "2") (pinfunction "2_2") (pintype "passive"))
      (node (ref "S4") (pin "3") (pinfunction "P_3") (pintype "passive"))
      (node (ref "S4") (pin "4") (pinfunction "P1_4") (pintype "passive"))
    )
    (net (code "62") (name "Net-(S5-P)") (class "Default")
      (node (ref "R33") (pin "1") (pinfunction "1_1") (pintype "passive"))
      (node (ref "R34") (pin "2") (pinfunction "2_2") (pintype "passive"))
      (node (ref "S5") (pin "3") (pinfunction "P_3") (pintype "passive"))
      (node (ref "S5") (pin "4") (pinfunction "P1_4") (pintype "passive"))
    )
    (net (code "63") (name "Net-(S6-P)") (class "Default")
      (node (ref "R34") (pin "1") (pinfunction "1_1") (pintype "passive"))
      (node (ref "R5") (pin "2") (pinfunction "2_2") (pintype "passive"))
      (node (ref "S6") (pin "3") (pinfunction "P_3") (pintype "passive"))
      (node (ref "S6") (pin "4") (pinfunction "P1_4") (pintype "passive"))
    )
    (net (code "64") (name "Net-(SV2-Pad2)") (class "Default")
      (node (ref "SV2") (pin "2") (pinfunction "2_2") (pintype "passive"))
      (node (ref "SV3") (pin "2") (pinfunction "2_2") (pintype "passive"))
    )
    (net (code "65") (name "VCC") (class "Default")
      (node (ref "C1") (pin "1") (pinfunction "1_1") (pintype "passive"))
      (node (ref "C10") (pin "1") (pinfunction "1_1") (pintype "passive"))
      (node (ref "C12") (pin "1") (pinfunction "1_1") (pintype "passive"))
      (node (ref "C18") (pin "1") (pinfunction "1_1") (pintype "passive"))
      (node (ref "C3") (pin "+") (pinfunction "+_+") (pintype "passive"))
      (node (ref "C6") (pin "1") (pinfunction "1_1") (pintype "passive"))
      (node (ref "C7") (pin "1") (pinfunction "1_1") (pintype "passive"))
      (node (ref "C9") (pin "1") (pinfunction "1_1") (pintype "passive"))
      (node (ref "IC1") (pin "3") (pinfunction "IN_3") (pintype "input"))
      (node (ref "IC2") (pin "1") (pinfunction "MR_1") (pintype "input"))
      (node (ref "IC2") (pin "2") (pinfunction "VCC_2") (pintype "power_in"))
      (node (ref "IC3") (pin "20") (pinfunction "VDD_20") (pintype "power_in"))
      (node (ref "IC5") (pin "2") (pinfunction "OUT_2") (pintype "passive"))
      (node (ref "J5") (pin "1") (pinfunction "1_1") (pintype "passive"))
      (node (ref "R2") (pin "2") (pinfunction "2_2") (pintype "passive"))
      (node (ref "R22") (pin "1") (pinfunction "1_1") (pintype "passive"))
      (node (ref "R23") (pin "2") (pinfunction "2_2") (pintype "passive"))
      (node (ref "R26") (pin "2") (pinfunction "2_2") (pintype "passive"))
      (node (ref "R3") (pin "2") (pinfunction "2_2") (pintype "passive"))
      (node (ref "R37") (pin "2") (pinfunction "2_2") (pintype "passive"))
      (node (ref "R38") (pin "2") (pinfunction "2_2") (pintype "passive"))
      (node (ref "R7") (pin "2") (pinfunction "2_2") (pintype "passive"))
      (node (ref "SV2") (pin "1") (pinfunction "1_1") (pintype "passive"))
    )
    (net (code "66") (name "VDD") (class "Default")
      (node (ref "C2") (pin "1") (pinfunction "1_1") (pintype "passive"))
      (node (ref "IC1") (pin "2") (pinfunction "OUT_2") (pintype "passive"))
      (node (ref "J1") (pin "VDD") (pinfunction "VDD_VDD") (pintype "power_in"))
      (node (ref "J5") (pin "10") (pinfunction "10_10") (pintype "passive"))
      (node (ref "R1") (pin "1") (pinfunction "1_1") (pintype "passive"))
      (node (ref "R11") (pin "1") (pinfunction "1_1") (pintype "passive"))
      (node (ref "R35") (pin "2") (pinfunction "2_2") (pintype "passive"))
      (node (ref "R36") (pin "2") (pinfunction "2_2") (pintype "passive"))
      (node (ref "SV2") (pin "3") (pinfunction "3_3") (pintype "passive"))
    )
    (net (code "67") (name "unconnected-(IC4A-R2OUT-Pad9)") (class "Default")
      (node (ref "IC4") (pin "9") (pinfunction "R2OUT_9") (pintype "output"))
    )
    (net (code "68") (name "unconnected-(IC4A-T1OUT-Pad14)") (class "Default")
      (node (ref "IC4") (pin "14") (pinfunction "T1OUT_14") (pintype "output"))
    )
  )
)
